# MCU.net
KiCad netlist of a schematic drawn in Altium Designer
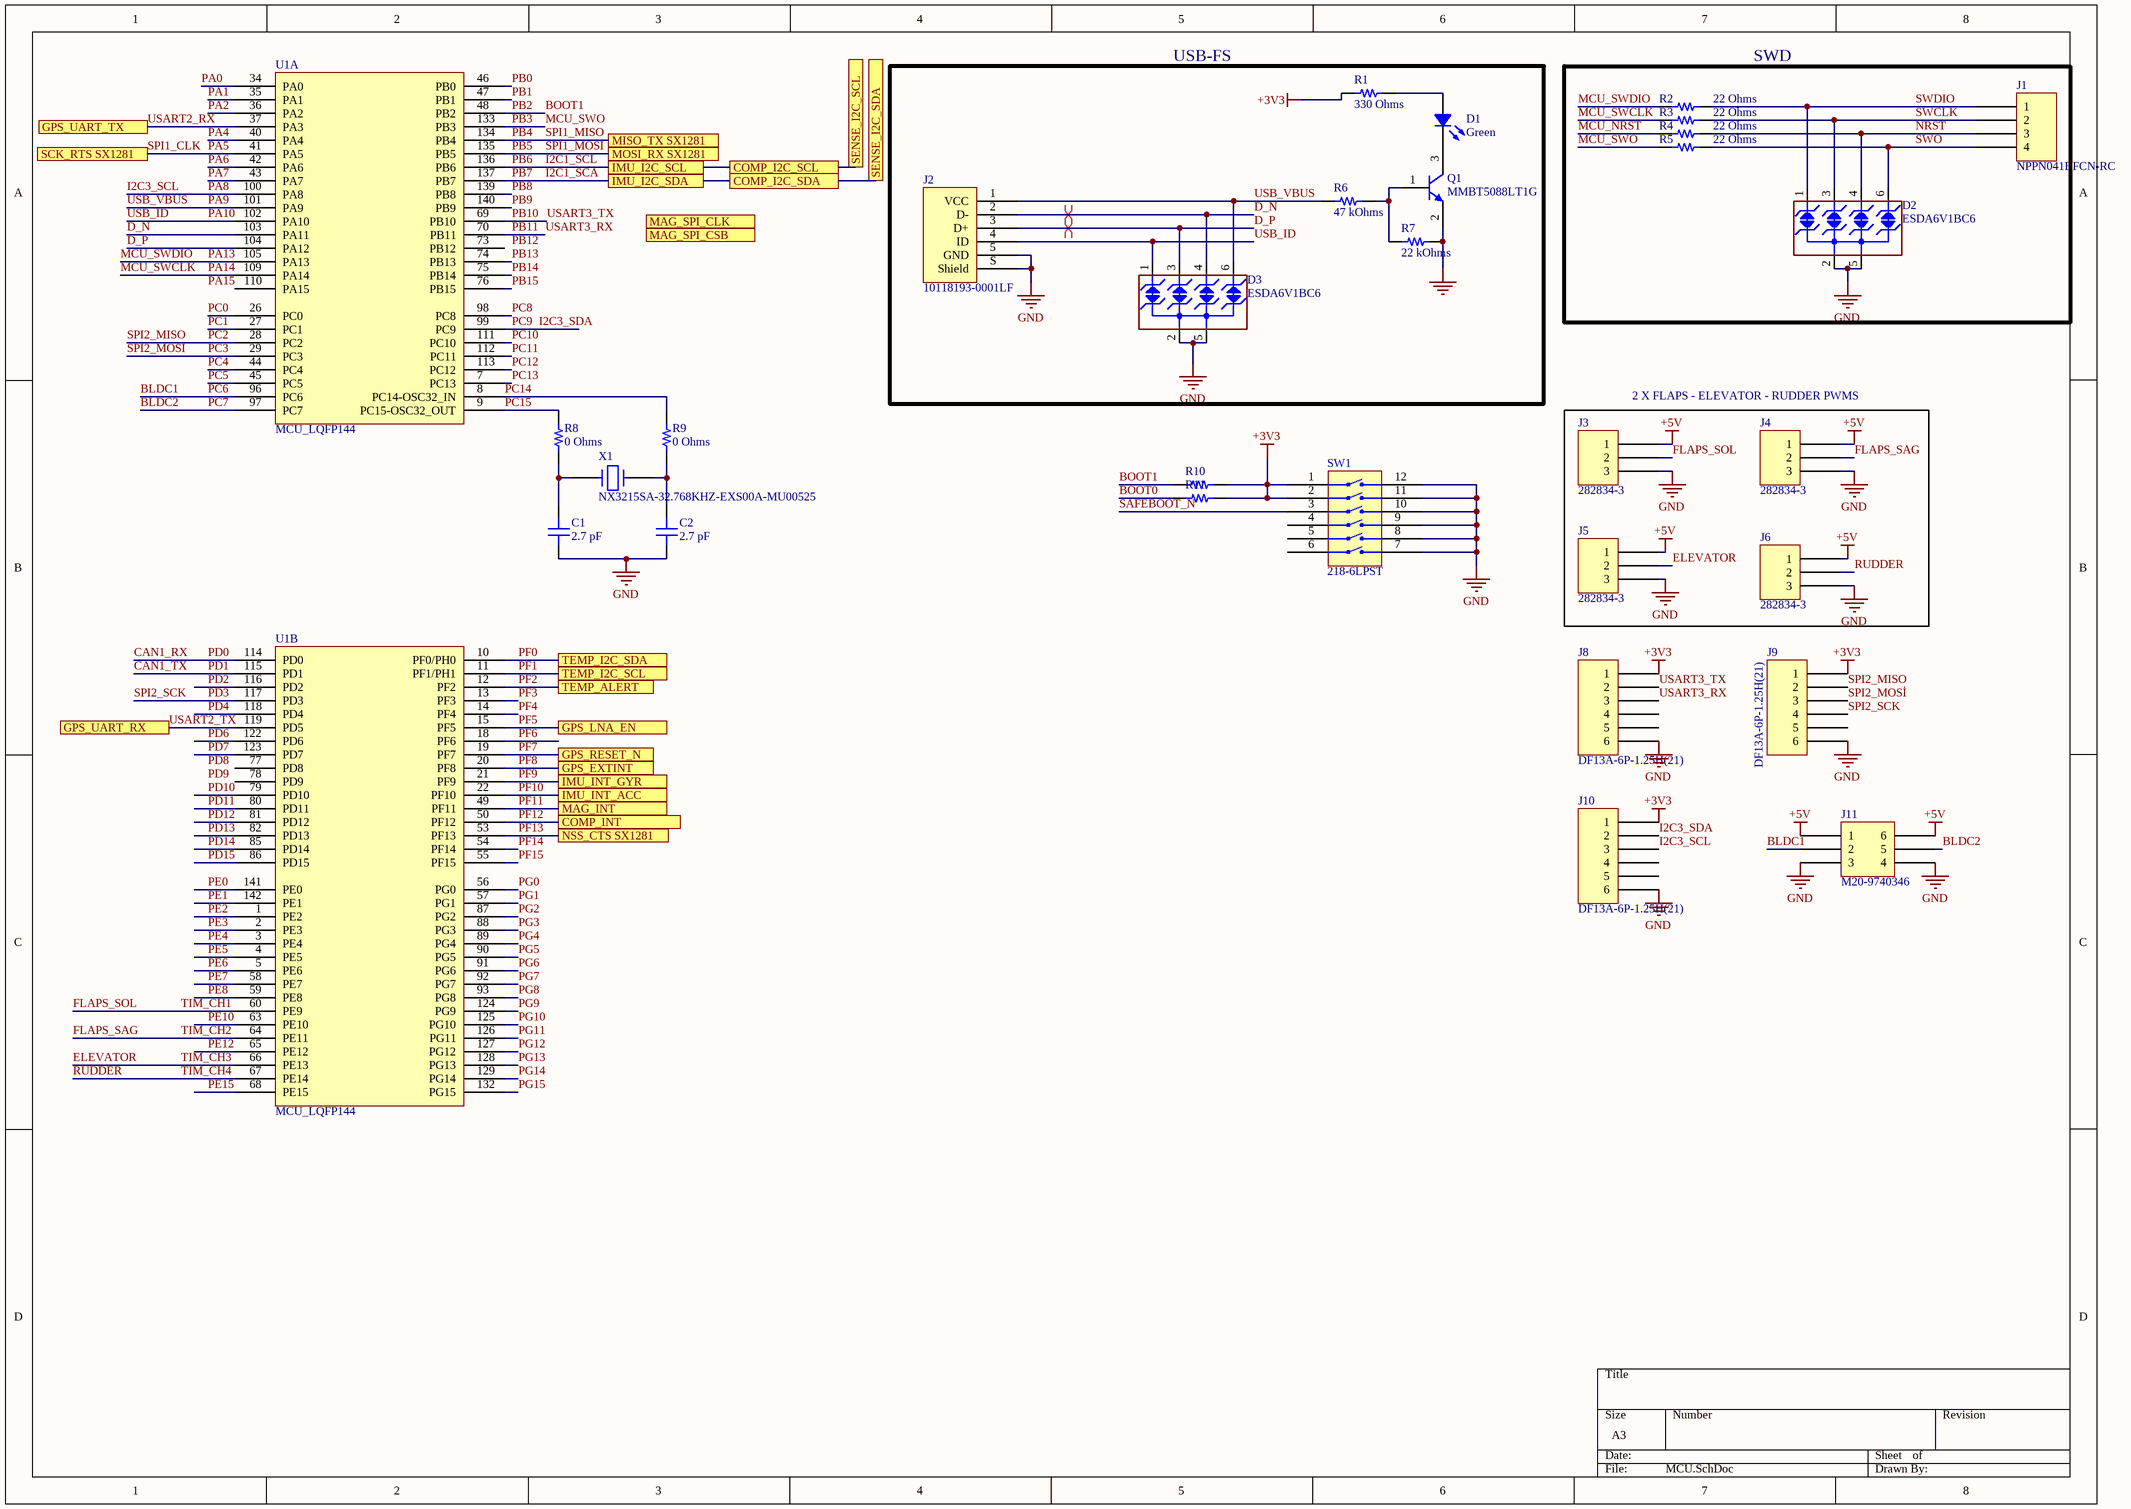
[diagram p0: MCU.SchDoc]

(export (version "E")
  (design (tool "Eeschema 10.0.6"))
  (components
    (comp (ref "C1")
      (value "2.7 pF")
      (footprint "CAP 0603_1608")
      (description "CAP CER 2.7PF 50V C0G/NPO 0603")
      (fields (field (name "PART NUMBER") "CC0603BRNPO9BN2R7") (field (name "MANUFACTURER") "Yageo"))
      (libsource (lib "Celestial Altium Library - altium_library") (part "Capacitor"))
    )
    (comp (ref "C2")
      (value "2.7 pF")
      (footprint "CAP 0603_1608")
      (description "CAP CER 2.7PF 50V C0G/NPO 0603")
      (fields (field (name "PART NUMBER") "CC0603BRNPO9BN2R7") (field (name "MANUFACTURER") "Yageo"))
      (libsource (lib "Celestial Altium Library - altium_library") (part "Capacitor"))
    )
    (comp (ref "D1")
      (value "Green")
      (footprint "LED 0603_1608 GREEN")
      (description "LED GREEN DIFFUSED CHIP SMD")
      (fields (field (name "PART NUMBER") "HSMG-C197") (field (name "MANUFACTURER") "Broadcom Limited"))
      (libsource (lib "Celestial Altium Library - altium_library") (part "LED"))
    )
    (comp (ref "D2")
      (value "ESDA6V1BC6")
      (footprint "SOT23-6L_STM")
      (description "4-line ESD protection")
      (libsource (lib "ECU_2_Project") (part "ESDA6V1BC6"))
    )
    (comp (ref "D3")
      (value "ESDA6V1BC6")
      (footprint "SOT23-6L_STM")
      (description "4-line ESD protection")
      (libsource (lib "Flight_controller v1.0") (part "ESDA6V1BC6"))
    )
    (comp (ref "J1")
      (value "NPPN041BFCN-RC")
      (footprint "SULLINS NPPN041BFCN")
      (description "CONN HDR 4POS 0.079 GOLD PCB")
      (fields (field (name "MANUFACTURER") "Sullins Connector Solutions"))
      (libsource (lib "Celestial Altium Library - altium_library") (part "4 Pin"))
    )
    (comp (ref "J2")
      (value "10118193-0001LF")
      (footprint "FCI USB 10118193-0001LF")
      (description "CONN RCPT USB2.0 MICRO B SMD R/A")
      (fields (field (name "MANUFACTURER") "Amphenol ICC (FCI)"))
      (libsource (lib "Celestial Altium Library - altium_library") (part "USB 2.0 Type B Micro"))
    )
    (comp (ref "J3")
      (value "282834-3")
      (footprint "TE 282834-3")
      (description "TERM BLK 3P SIDE ENT 2.54MM PCB")
      (fields (field (name "MANUFACTURER") "TE Connectivity AMP Connectors") (field (name "VOLTAGE") "150V"))
      (libsource (lib "Celestial Altium Library - altium_library") (part "3 Pin"))
    )
    (comp (ref "J4")
      (value "282834-3")
      (footprint "TE 282834-3")
      (description "TERM BLK 3P SIDE ENT 2.54MM PCB")
      (fields (field (name "MANUFACTURER") "TE Connectivity AMP Connectors") (field (name "VOLTAGE") "150V"))
      (libsource (lib "Celestial Altium Library - altium_library") (part "3 Pin"))
    )
    (comp (ref "J5")
      (value "282834-3")
      (footprint "TE 282834-3")
      (description "TERM BLK 3P SIDE ENT 2.54MM PCB")
      (fields (field (name "MANUFACTURER") "TE Connectivity AMP Connectors") (field (name "VOLTAGE") "150V"))
      (libsource (lib "Celestial Altium Library - altium_library") (part "3 Pin"))
    )
    (comp (ref "J6")
      (value "282834-3")
      (footprint "TE 282834-3")
      (description "TERM BLK 3P SIDE ENT 2.54MM PCB")
      (fields (field (name "MANUFACTURER") "TE Connectivity AMP Connectors") (field (name "VOLTAGE") "150V"))
      (libsource (lib "Celestial Altium Library - altium_library") (part "3 Pin"))
    )
    (comp (ref "J8")
      (value "DF13A-6P-1.25H(21)")
      (footprint "HIROSE DF13A-6P-1.25H")
      (description "CONN HEADER SMD R/A 6POS 1.25MM")
      (fields (field (name "MANUFACTURER") "Hirose Electric Co Ltd"))
      (libsource (lib "Celestial Altium Library - altium_library") (part "6 Pin"))
    )
    (comp (ref "J9")
      (value "DF13A-6P-1.25H(21)")
      (footprint "HIROSE DF13A-6P-1.25H")
      (description "CONN HEADER SMD R/A 6POS 1.25MM")
      (fields (field (name "MANUFACTURER") "Hirose Electric Co Ltd"))
      (libsource (lib "Celestial Altium Library - altium_library") (part "6 Pin"))
    )
    (comp (ref "J10")
      (value "DF13A-6P-1.25H(21)")
      (footprint "HIROSE DF13A-6P-1.25H")
      (description "CONN HEADER SMD R/A 6POS 1.25MM")
      (fields (field (name "MANUFACTURER") "Hirose Electric Co Ltd"))
      (libsource (lib "Celestial Altium Library - altium_library") (part "6 Pin"))
    )
    (comp (ref "J11")
      (value "M20-9740346")
      (footprint "HARWIN M20-9740345")
      (description "CONN HEADER R/A 6POS 2.54MM")
      (fields (field (name "MANUFACTURER") "Harwin Inc."))
      (libsource (lib "Celestial Altium Library - altium_library") (part "2X3 PIN DU"))
    )
    (comp (ref "Q1")
      (value "MMBT5088LT1G")
      (footprint "ON SEMI SOT-23-3")
      (description "TRANS NPN 30V 0.05A SOT23")
      (fields (field (name "MANUFACTURER") "ON Semiconductor"))
      (libsource (lib "Celestial Altium Library - altium_library") (part "ON SEMI NPN SOT-23-3"))
    )
    (comp (ref "R1")
      (value "330 Ohms")
      (footprint "RES 0603_1608")
      (description "RES 330 OHM 1% 1/10W 0603")
      (fields (field (name "PART NUMBER") "RC0603FR-07330RL") (field (name "MANUFACTURER") "Yageo"))
      (libsource (lib "Celestial Altium Library - altium_library") (part "Resistor"))
    )
    (comp (ref "R2")
      (value "22 Ohms")
      (footprint "RES 0603_1608")
      (description "RES 22 OHM 1% 1/10W 0603")
      (fields (field (name "PART NUMBER") "RC0603FR-0722RL") (field (name "MANUFACTURER") "Yageo"))
      (libsource (lib "Celestial Altium Library - altium_library") (part "Resistor"))
    )
    (comp (ref "R3")
      (value "22 Ohms")
      (footprint "RES 0603_1608")
      (description "RES 22 OHM 1% 1/10W 0603")
      (fields (field (name "PART NUMBER") "RC0603FR-0722RL") (field (name "MANUFACTURER") "Yageo"))
      (libsource (lib "Celestial Altium Library - altium_library") (part "Resistor"))
    )
    (comp (ref "R4")
      (value "22 Ohms")
      (footprint "RES 0603_1608")
      (description "RES 22 OHM 1% 1/10W 0603")
      (fields (field (name "PART NUMBER") "RC0603FR-0722RL") (field (name "MANUFACTURER") "Yageo"))
      (libsource (lib "Celestial Altium Library - altium_library") (part "Resistor"))
    )
    (comp (ref "R5")
      (value "22 Ohms")
      (footprint "RES 0603_1608")
      (description "RES 22 OHM 1% 1/10W 0603")
      (fields (field (name "PART NUMBER") "RC0603FR-0722RL") (field (name "MANUFACTURER") "Yageo"))
      (libsource (lib "Celestial Altium Library - altium_library") (part "Resistor"))
    )
    (comp (ref "R6")
      (value "47 kOhms")
      (footprint "RES 0603_1608")
      (description "RES 47K OHM 1% 1/10W 0603")
      (fields (field (name "PART NUMBER") "RC0603FR-0747KL") (field (name "MANUFACTURER") "Yageo"))
      (libsource (lib "Celestial Altium Library - altium_library") (part "Resistor"))
    )
    (comp (ref "R7")
      (value "22 kOhms")
      (footprint "RES 0603_1608")
      (description "RES 22K OHM 1% 1/10W 0603")
      (fields (field (name "PART NUMBER") "RC0603FR-0722KL") (field (name "MANUFACTURER") "Yageo"))
      (libsource (lib "Celestial Altium Library - altium_library") (part "Resistor"))
    )
    (comp (ref "R8")
      (value "0 Ohms")
      (footprint "RES 0603_1608")
      (description "RES 0 OHM JUMPER 1/10W 0603")
      (fields (field (name "PART NUMBER") "RC0603JR-070RL") (field (name "MANUFACTURER") "Yageo"))
      (libsource (lib "Celestial Altium Library - altium_library") (part "Resistor"))
    )
    (comp (ref "R9")
      (value "0 Ohms")
      (footprint "RES 0603_1608")
      (description "RES 0 OHM JUMPER 1/10W 0603")
      (fields (field (name "PART NUMBER") "RC0603JR-070RL") (field (name "MANUFACTURER") "Yageo"))
      (libsource (lib "Celestial Altium Library - altium_library") (part "Resistor"))
    )
    (comp (ref "R10")
      (value "100 kOhms")
      (footprint "RES 0603_1608")
      (description "RES 100K OHM 1% 1/10W 0603")
      (fields (field (name "PART NUMBER") "RC0603FR-07100KL") (field (name "MANUFACTURER") "Yageo"))
      (libsource (lib "Celestial Altium Library - altium_library") (part "Resistor"))
    )
    (comp (ref "R11")
      (value "10 kOhms")
      (footprint "RES 0603_1608")
      (description "RES 10K OHM 1% 1/10W 0603")
      (fields (field (name "PART NUMBER") "RC0603FR-0710KL") (field (name "MANUFACTURER") "Yageo"))
      (libsource (lib "Celestial Altium Library - altium_library") (part "Resistor"))
    )
    (comp (ref "SW1")
      (value "218-6LPST")
      (footprint "CTS 218-6LPJ")
      (description "SWITCH SLIDE DIP SPST 25MA 24V")
      (fields (field (name "MANUFACTURER") "CTS Electrocomponents"))
      (libsource (lib "Celestial Altium Library - altium_library") (part "DIP SW 6P"))
    )
    (comp (ref "U1")
      (value "MCU_LQFP144")
      (footprint "LQFP144-20x20mm")
      (libsource (lib "MB1137") (part "MCU_LQFP144"))
    )
    (comp (ref "X1")
      (value "NX3215SA-32.768KHZ-EXS00A-MU00525")
      (footprint "XTAL_NX3215SA-32.768KHZ-EXS00A-MU00525_NDK")
      (description "Crystal")
      (libsource (lib "Flight_controller v1.0") (part "CRYSTAL_32K"))
    )
  )
  (nets
    (net (code "1") (name "+3V3") (class "Default")
      (node (ref "J10") (pin "1") (pinfunction "1_1") (pintype "passive"))
      (node (ref "J8") (pin "1") (pinfunction "1_1") (pintype "passive"))
      (node (ref "J9") (pin "1") (pinfunction "1_1") (pintype "passive"))
      (node (ref "R1") (pin "2") (pinfunction "2_2") (pintype "passive"))
      (node (ref "R10") (pin "2") (pinfunction "2_2") (pintype "passive"))
      (node (ref "R11") (pin "2") (pinfunction "2_2") (pintype "passive"))
      (node (ref "SW1") (pin "1") (pinfunction "GND_1") (pintype "passive"))
      (node (ref "SW1") (pin "2") (pinfunction "GND_2") (pintype "passive"))
    )
    (net (code "2") (name "+5V") (class "Default")
      (node (ref "J11") (pin "1") (pinfunction "1_1") (pintype "passive"))
      (node (ref "J11") (pin "6") (pinfunction "6_6") (pintype "passive"))
      (node (ref "J3") (pin "1") (pinfunction "1_1") (pintype "passive"))
      (node (ref "J4") (pin "1") (pinfunction "1_1") (pintype "passive"))
      (node (ref "J5") (pin "1") (pinfunction "1_1") (pintype "passive"))
      (node (ref "J6") (pin "1") (pinfunction "1_1") (pintype "passive"))
    )
    (net (code "3") (name "/BLDC1") (class "Default")
      (node (ref "J11") (pin "2") (pinfunction "2_2") (pintype "passive"))
      (node (ref "U1") (pin "96") (pinfunction "PC6_96") (pintype "passive"))
    )
    (net (code "4") (name "/BLDC2") (class "Default")
      (node (ref "J11") (pin "5") (pinfunction "5_5") (pintype "passive"))
      (node (ref "U1") (pin "97") (pinfunction "PC7_97") (pintype "passive"))
    )
    (net (code "5") (name "/BOOT0") (class "Default")
      (node (ref "R11") (pin "1") (pinfunction "1_1") (pintype "passive"))
    )
    (net (code "6") (name "/BOOT1") (class "Default")
      (node (ref "R10") (pin "1") (pinfunction "1_1") (pintype "passive"))
      (node (ref "U1") (pin "48") (pinfunction "PB2_48") (pintype "passive"))
    )
    (net (code "7") (name "/CAN1_RX") (class "Default")
      (node (ref "U1") (pin "114") (pinfunction "PD0_114") (pintype "passive"))
    )
    (net (code "8") (name "/CAN1_TX") (class "Default")
      (node (ref "U1") (pin "115") (pinfunction "PD1_115") (pintype "passive"))
    )
    (net (code "9") (name "/D_N") (class "Default")
      (node (ref "D3") (pin "4") (pinfunction "IO3_4") (pintype "passive"))
      (node (ref "J2") (pin "2") (pinfunction "D-_2") (pintype "passive"))
      (node (ref "U1") (pin "103") (pinfunction "PA11_103") (pintype "passive"))
    )
    (net (code "10") (name "/D_P") (class "Default")
      (node (ref "D3") (pin "3") (pinfunction "GND_3") (pintype "passive"))
      (node (ref "J2") (pin "3") (pinfunction "D+_3") (pintype "passive"))
      (node (ref "U1") (pin "104") (pinfunction "PA12_104") (pintype "passive"))
    )
    (net (code "11") (name "/ELEVATOR") (class "Default")
      (node (ref "J5") (pin "2") (pinfunction "2_2") (pintype "passive"))
      (node (ref "U1") (pin "66") (pinfunction "PE13_66") (pintype "passive"))
    )
    (net (code "12") (name "/FLAPS_SAG") (class "Default")
      (node (ref "J4") (pin "2") (pinfunction "2_2") (pintype "passive"))
      (node (ref "U1") (pin "64") (pinfunction "PE11_64") (pintype "passive"))
    )
    (net (code "13") (name "/FLAPS_SOL") (class "Default")
      (node (ref "J3") (pin "2") (pinfunction "2_2") (pintype "passive"))
      (node (ref "U1") (pin "60") (pinfunction "PE9_60") (pintype "passive"))
    )
    (net (code "14") (name "/I2C1_SCA") (class "Default")
      (node (ref "U1") (pin "137") (pinfunction "PB7_137") (pintype "passive"))
    )
    (net (code "15") (name "/I2C1_SCL") (class "Default")
      (node (ref "U1") (pin "136") (pinfunction "PB6_136") (pintype "passive"))
    )
    (net (code "16") (name "/I2C3_SCL") (class "Default")
      (node (ref "J10") (pin "3") (pinfunction "3_3") (pintype "passive"))
      (node (ref "U1") (pin "100") (pinfunction "PA8_100") (pintype "passive"))
    )
    (net (code "17") (name "/I2C3_SDA") (class "Default")
      (node (ref "J10") (pin "2") (pinfunction "2_2") (pintype "passive"))
      (node (ref "U1") (pin "99") (pinfunction "PC9_99") (pintype "passive"))
    )
    (net (code "20") (name "/MCU_NRST") (class "Default")
      (node (ref "R4") (pin "1") (pinfunction "1_1") (pintype "passive"))
    )
    (net (code "21") (name "/MCU_SWCLK") (class "Default")
      (node (ref "R3") (pin "1") (pinfunction "1_1") (pintype "passive"))
      (node (ref "U1") (pin "109") (pinfunction "PA14_109") (pintype "passive"))
    )
    (net (code "22") (name "/MCU_SWDIO") (class "Default")
      (node (ref "R2") (pin "1") (pinfunction "1_1") (pintype "passive"))
      (node (ref "U1") (pin "105") (pinfunction "PA13_105") (pintype "passive"))
    )
    (net (code "23") (name "/MCU_SWO") (class "Default")
      (node (ref "R5") (pin "1") (pinfunction "1_1") (pintype "passive"))
      (node (ref "U1") (pin "133") (pinfunction "PB3_133") (pintype "passive"))
    )
    (net (code "24") (name "/NRST") (class "Default")
      (node (ref "D2") (pin "4") (pinfunction "IO3_4") (pintype "passive"))
      (node (ref "J1") (pin "3") (pinfunction "3_3") (pintype "passive"))
      (node (ref "R4") (pin "2") (pinfunction "2_2") (pintype "passive"))
    )
    (net (code "25") (name "/PA0") (class "Default")
      (node (ref "U1") (pin "34") (pinfunction "PA0_34") (pintype "passive"))
    )
    (net (code "26") (name "/PA1") (class "Default")
      (node (ref "U1") (pin "35") (pinfunction "PA1_35") (pintype "passive"))
    )
    (net (code "27") (name "/PA2") (class "Default")
      (node (ref "U1") (pin "36") (pinfunction "PA2_36") (pintype "passive"))
    )
    (net (code "28") (name "/PA4") (class "Default")
      (node (ref "U1") (pin "40") (pinfunction "PA4_40") (pintype "passive"))
    )
    (net (code "29") (name "/PA5") (class "Default")
      (node (ref "U1") (pin "41") (pinfunction "PA5_41") (pintype "passive"))
    )
    (net (code "30") (name "/PA6") (class "Default")
      (node (ref "U1") (pin "42") (pinfunction "PA6_42") (pintype "passive"))
    )
    (net (code "31") (name "/PA7") (class "Default")
      (node (ref "U1") (pin "43") (pinfunction "PA7_43") (pintype "passive"))
    )
    (net (code "32") (name "/PA9") (class "Default")
      (node (ref "D3") (pin "6") (pinfunction "NC_6") (pintype "passive"))
      (node (ref "J2") (pin "1") (pinfunction "VCC_1") (pintype "passive"))
      (node (ref "R6") (pin "1") (pinfunction "1_1") (pintype "passive"))
      (node (ref "U1") (pin "101") (pinfunction "PA9_101") (pintype "passive"))
    )
    (net (code "33") (name "/PA10") (class "Default")
      (node (ref "D3") (pin "1") (pinfunction "IO1_1") (pintype "passive"))
      (node (ref "J2") (pin "4") (pinfunction "ID_4") (pintype "passive"))
      (node (ref "U1") (pin "102") (pinfunction "PA10_102") (pintype "passive"))
    )
    (net (code "35") (name "/PB0") (class "Default")
      (node (ref "U1") (pin "46") (pinfunction "PB0_46") (pintype "passive"))
    )
    (net (code "36") (name "/PB1") (class "Default")
      (node (ref "U1") (pin "47") (pinfunction "PB1_47") (pintype "passive"))
    )
    (net (code "37") (name "/PB4") (class "Default")
      (node (ref "U1") (pin "134") (pinfunction "PB4_134") (pintype "passive"))
    )
    (net (code "38") (name "/PB5") (class "Default")
      (node (ref "U1") (pin "135") (pinfunction "PB5_135") (pintype "passive"))
    )
    (net (code "39") (name "/PB8") (class "Default")
      (node (ref "U1") (pin "139") (pinfunction "PB8_139") (pintype "passive"))
    )
    (net (code "40") (name "/PB9") (class "Default")
      (node (ref "U1") (pin "140") (pinfunction "PB9_140") (pintype "passive"))
    )
    (net (code "41") (name "/PB10") (class "Default")
      (node (ref "J8") (pin "2") (pinfunction "2_2") (pintype "passive"))
      (node (ref "U1") (pin "69") (pinfunction "PB10_69") (pintype "passive"))
    )
    (net (code "42") (name "/PB11") (class "Default")
      (node (ref "J8") (pin "3") (pinfunction "3_3") (pintype "passive"))
      (node (ref "U1") (pin "70") (pinfunction "PB11_70") (pintype "passive"))
    )
    (net (code "44") (name "/PB13") (class "Default")
      (node (ref "U1") (pin "74") (pinfunction "PB13_74") (pintype "passive"))
    )
    (net (code "45") (name "/PB14") (class "Default")
      (node (ref "U1") (pin "75") (pinfunction "PB14_75") (pintype "passive"))
    )
    (net (code "46") (name "/PB15") (class "Default")
      (node (ref "U1") (pin "76") (pinfunction "PB15_76") (pintype "passive"))
    )
    (net (code "47") (name "/PC0") (class "Default")
      (node (ref "U1") (pin "26") (pinfunction "PC0_26") (pintype "passive"))
    )
    (net (code "48") (name "/PC1") (class "Default")
      (node (ref "U1") (pin "27") (pinfunction "PC1_27") (pintype "passive"))
    )
    (net (code "49") (name "/PC2") (class "Default")
      (node (ref "J9") (pin "2") (pinfunction "2_2") (pintype "passive"))
      (node (ref "U1") (pin "28") (pinfunction "PC2_28") (pintype "passive"))
    )
    (net (code "50") (name "/PC3") (class "Default")
      (node (ref "J9") (pin "3") (pinfunction "3_3") (pintype "passive"))
      (node (ref "U1") (pin "29") (pinfunction "PC3_29") (pintype "passive"))
    )
    (net (code "51") (name "/PC4") (class "Default")
      (node (ref "U1") (pin "44") (pinfunction "PC4_44") (pintype "passive"))
    )
    (net (code "52") (name "/PC5") (class "Default")
      (node (ref "U1") (pin "45") (pinfunction "PC5_45") (pintype "passive"))
    )
    (net (code "53") (name "/PC8") (class "Default")
      (node (ref "U1") (pin "98") (pinfunction "PC8_98") (pintype "passive"))
    )
    (net (code "54") (name "/PC10") (class "Default")
      (node (ref "U1") (pin "111") (pinfunction "PC10_111") (pintype "passive"))
    )
    (net (code "55") (name "/PC11") (class "Default")
      (node (ref "U1") (pin "112") (pinfunction "PC11_112") (pintype "passive"))
    )
    (net (code "56") (name "/PC12") (class "Default")
      (node (ref "U1") (pin "113") (pinfunction "PC12_113") (pintype "passive"))
    )
    (net (code "57") (name "/PC13") (class "Default")
      (node (ref "U1") (pin "7") (pinfunction "PC13_7") (pintype "passive"))
    )
    (net (code "58") (name "/PC14") (class "Default")
      (node (ref "R9") (pin "2") (pinfunction "2_2") (pintype "passive"))
      (node (ref "U1") (pin "8") (pinfunction "PC14-OSC32_IN_8") (pintype "passive"))
    )
    (net (code "59") (name "/PC15") (class "Default")
      (node (ref "R8") (pin "2") (pinfunction "2_2") (pintype "passive"))
      (node (ref "U1") (pin "9") (pinfunction "PC15-OSC32_OUT_9") (pintype "passive"))
    )
    (net (code "60") (name "/PD2") (class "Default")
      (node (ref "U1") (pin "116") (pinfunction "PD2_116") (pintype "passive"))
    )
    (net (code "61") (name "/PD3") (class "Default")
      (node (ref "J9") (pin "4") (pinfunction "4_4") (pintype "passive"))
      (node (ref "U1") (pin "117") (pinfunction "PD3_117") (pintype "passive"))
    )
    (net (code "62") (name "/PD4") (class "Default")
      (node (ref "U1") (pin "118") (pinfunction "PD4_118") (pintype "passive"))
    )
    (net (code "63") (name "/PD6") (class "Default")
      (node (ref "U1") (pin "122") (pinfunction "PD6_122") (pintype "passive"))
    )
    (net (code "64") (name "/PD7") (class "Default")
      (node (ref "U1") (pin "123") (pinfunction "PD7_123") (pintype "passive"))
    )
    (net (code "67") (name "/PD10") (class "Default")
      (node (ref "U1") (pin "79") (pinfunction "PD10_79") (pintype "passive"))
    )
    (net (code "68") (name "/PD11") (class "Default")
      (node (ref "U1") (pin "80") (pinfunction "PD11_80") (pintype "passive"))
    )
    (net (code "69") (name "/PD12") (class "Default")
      (node (ref "U1") (pin "81") (pinfunction "PD12_81") (pintype "passive"))
    )
    (net (code "70") (name "/PD13") (class "Default")
      (node (ref "U1") (pin "82") (pinfunction "PD13_82") (pintype "passive"))
    )
    (net (code "71") (name "/PD14") (class "Default")
      (node (ref "U1") (pin "85") (pinfunction "PD14_85") (pintype "passive"))
    )
    (net (code "72") (name "/PD15") (class "Default")
      (node (ref "U1") (pin "86") (pinfunction "PD15_86") (pintype "passive"))
    )
    (net (code "73") (name "/PE0") (class "Default")
      (node (ref "U1") (pin "141") (pinfunction "PE0_141") (pintype "passive"))
    )
    (net (code "74") (name "/PE1") (class "Default")
      (node (ref "U1") (pin "142") (pinfunction "PE1_142") (pintype "passive"))
    )
    (net (code "75") (name "/PE2") (class "Default")
      (node (ref "U1") (pin "1") (pinfunction "PE2_1") (pintype "passive"))
    )
    (net (code "76") (name "/PE3") (class "Default")
      (node (ref "U1") (pin "2") (pinfunction "PE3_2") (pintype "passive"))
    )
    (net (code "77") (name "/PE4") (class "Default")
      (node (ref "U1") (pin "3") (pinfunction "PE4_3") (pintype "passive"))
    )
    (net (code "78") (name "/PE5") (class "Default")
      (node (ref "U1") (pin "4") (pinfunction "PE5_4") (pintype "passive"))
    )
    (net (code "79") (name "/PE6") (class "Default")
      (node (ref "U1") (pin "5") (pinfunction "PE6_5") (pintype "passive"))
    )
    (net (code "80") (name "/PE7") (class "Default")
      (node (ref "U1") (pin "58") (pinfunction "PE7_58") (pintype "passive"))
    )
    (net (code "81") (name "/PE8") (class "Default")
      (node (ref "U1") (pin "59") (pinfunction "PE8_59") (pintype "passive"))
    )
    (net (code "82") (name "/PE10") (class "Default")
      (node (ref "U1") (pin "63") (pinfunction "PE10_63") (pintype "passive"))
    )
    (net (code "83") (name "/PE12") (class "Default")
      (node (ref "U1") (pin "65") (pinfunction "PE12_65") (pintype "passive"))
    )
    (net (code "84") (name "/PE15") (class "Default")
      (node (ref "U1") (pin "68") (pinfunction "PE15_68") (pintype "passive"))
    )
    (net (code "85") (name "/PF0") (class "Default")
      (node (ref "U1") (pin "10") (pinfunction "PF0/PH0_10") (pintype "passive"))
    )
    (net (code "86") (name "/PF1") (class "Default")
      (node (ref "U1") (pin "11") (pinfunction "PF1/PH1_11") (pintype "passive"))
    )
    (net (code "87") (name "/PF2") (class "Default")
      (node (ref "U1") (pin "12") (pinfunction "PF2_12") (pintype "passive"))
    )
    (net (code "88") (name "/PF3") (class "Default")
      (node (ref "U1") (pin "13") (pinfunction "PF3_13") (pintype "passive"))
    )
    (net (code "89") (name "/PF4") (class "Default")
      (node (ref "U1") (pin "14") (pinfunction "PF4_14") (pintype "passive"))
    )
    (net (code "90") (name "/PF5") (class "Default")
      (node (ref "U1") (pin "15") (pinfunction "PF5_15") (pintype "passive"))
    )
    (net (code "91") (name "/PF6") (class "Default")
      (node (ref "U1") (pin "18") (pinfunction "PF6_18") (pintype "passive"))
    )
    (net (code "92") (name "/PF7") (class "Default")
      (node (ref "U1") (pin "19") (pinfunction "PF7_19") (pintype "passive"))
    )
    (net (code "93") (name "/PF8") (class "Default")
      (node (ref "U1") (pin "20") (pinfunction "PF8_20") (pintype "passive"))
    )
    (net (code "94") (name "/PF9") (class "Default")
      (node (ref "U1") (pin "21") (pinfunction "PF9_21") (pintype "passive"))
    )
    (net (code "95") (name "/PF10") (class "Default")
      (node (ref "U1") (pin "22") (pinfunction "PF10_22") (pintype "passive"))
    )
    (net (code "96") (name "/PF11") (class "Default")
      (node (ref "U1") (pin "49") (pinfunction "PF11_49") (pintype "passive"))
    )
    (net (code "97") (name "/PF12") (class "Default")
      (node (ref "U1") (pin "50") (pinfunction "PF12_50") (pintype "passive"))
    )
    (net (code "98") (name "/PF13") (class "Default")
      (node (ref "U1") (pin "53") (pinfunction "PF13_53") (pintype "passive"))
    )
    (net (code "99") (name "/PF14") (class "Default")
      (node (ref "U1") (pin "54") (pinfunction "PF14_54") (pintype "passive"))
    )
    (net (code "100") (name "/PF15") (class "Default")
      (node (ref "U1") (pin "55") (pinfunction "PF15_55") (pintype "passive"))
    )
    (net (code "101") (name "/PG0") (class "Default")
      (node (ref "U1") (pin "56") (pinfunction "PG0_56") (pintype "passive"))
    )
    (net (code "102") (name "/PG1") (class "Default")
      (node (ref "U1") (pin "57") (pinfunction "PG1_57") (pintype "passive"))
    )
    (net (code "103") (name "/PG2") (class "Default")
      (node (ref "U1") (pin "87") (pinfunction "PG2_87") (pintype "passive"))
    )
    (net (code "104") (name "/PG3") (class "Default")
      (node (ref "U1") (pin "88") (pinfunction "PG3_88") (pintype "passive"))
    )
    (net (code "105") (name "/PG4") (class "Default")
      (node (ref "U1") (pin "89") (pinfunction "PG4_89") (pintype "passive"))
    )
    (net (code "106") (name "/PG5") (class "Default")
      (node (ref "U1") (pin "90") (pinfunction "PG5_90") (pintype "passive"))
    )
    (net (code "107") (name "/PG6") (class "Default")
      (node (ref "U1") (pin "91") (pinfunction "PG6_91") (pintype "passive"))
    )
    (net (code "108") (name "/PG7") (class "Default")
      (node (ref "U1") (pin "92") (pinfunction "PG7_92") (pintype "passive"))
    )
    (net (code "109") (name "/PG8") (class "Default")
      (node (ref "U1") (pin "93") (pinfunction "PG8_93") (pintype "passive"))
    )
    (net (code "110") (name "/PG9") (class "Default")
      (node (ref "U1") (pin "124") (pinfunction "PG9_124") (pintype "passive"))
    )
    (net (code "111") (name "/PG10") (class "Default")
      (node (ref "U1") (pin "125") (pinfunction "PG10_125") (pintype "passive"))
    )
    (net (code "112") (name "/PG11") (class "Default")
      (node (ref "U1") (pin "126") (pinfunction "PG11_126") (pintype "passive"))
    )
    (net (code "113") (name "/PG12") (class "Default")
      (node (ref "U1") (pin "127") (pinfunction "PG12_127") (pintype "passive"))
    )
    (net (code "114") (name "/PG13") (class "Default")
      (node (ref "U1") (pin "128") (pinfunction "PG13_128") (pintype "passive"))
    )
    (net (code "115") (name "/PG14") (class "Default")
      (node (ref "U1") (pin "129") (pinfunction "PG14_129") (pintype "passive"))
    )
    (net (code "116") (name "/PG15") (class "Default")
      (node (ref "U1") (pin "132") (pinfunction "PG15_132") (pintype "passive"))
    )
    (net (code "117") (name "/RUDDER") (class "Default")
      (node (ref "J6") (pin "2") (pinfunction "2_2") (pintype "passive"))
      (node (ref "U1") (pin "67") (pinfunction "PE14_67") (pintype "passive"))
    )
    (net (code "118") (name "/SAFEBOOT_N") (class "Default")
      (node (ref "SW1") (pin "3") (pinfunction "GND_3") (pintype "passive"))
    )
    (net (code "119") (name "/SWCLK") (class "Default")
      (node (ref "D2") (pin "3") (pinfunction "GND_3") (pintype "passive"))
      (node (ref "J1") (pin "2") (pinfunction "2_2") (pintype "passive"))
      (node (ref "R3") (pin "2") (pinfunction "2_2") (pintype "passive"))
    )
    (net (code "120") (name "/SWDIO") (class "Default")
      (node (ref "D2") (pin "1") (pinfunction "IO1_1") (pintype "passive"))
      (node (ref "J1") (pin "1") (pinfunction "1_1") (pintype "passive"))
      (node (ref "R2") (pin "2") (pinfunction "2_2") (pintype "passive"))
    )
    (net (code "121") (name "/SWO") (class "Default")
      (node (ref "D2") (pin "6") (pinfunction "NC_6") (pintype "passive"))
      (node (ref "J1") (pin "4") (pinfunction "4_4") (pintype "passive"))
      (node (ref "R5") (pin "2") (pinfunction "2_2") (pintype "passive"))
    )
    (net (code "122") (name "/USART2_RX") (class "Default")
      (node (ref "U1") (pin "37") (pinfunction "PA3_37") (pintype "passive"))
    )
    (net (code "123") (name "/USART2_TX") (class "Default")
      (node (ref "U1") (pin "119") (pinfunction "PD5_119") (pintype "passive"))
    )
    (net (code "124") (name "GND") (class "Default")
      (node (ref "C1") (pin "1") (pinfunction "1_1") (pintype "passive"))
      (node (ref "C2") (pin "1") (pinfunction "1_1") (pintype "passive"))
      (node (ref "D2") (pin "2") (pinfunction "IO2_2") (pintype "passive"))
      (node (ref "D2") (pin "5") (pinfunction "IO4_5") (pintype "passive"))
      (node (ref "D3") (pin "2") (pinfunction "IO2_2") (pintype "passive"))
      (node (ref "D3") (pin "5") (pinfunction "IO4_5") (pintype "passive"))
      (node (ref "J10") (pin "6") (pinfunction "6_6") (pintype "passive"))
      (node (ref "J11") (pin "3") (pinfunction "3_3") (pintype "passive"))
      (node (ref "J11") (pin "4") (pinfunction "4_4") (pintype "passive"))
      (node (ref "J2") (pin "5") (pinfunction "GND_5") (pintype "passive"))
      (node (ref "J2") (pin "S") (pinfunction "Shield_S") (pintype "passive"))
      (node (ref "J3") (pin "3") (pinfunction "3_3") (pintype "passive"))
      (node (ref "J4") (pin "3") (pinfunction "3_3") (pintype "passive"))
      (node (ref "J5") (pin "3") (pinfunction "3_3") (pintype "passive"))
      (node (ref "J6") (pin "3") (pinfunction "3_3") (pintype "passive"))
      (node (ref "J8") (pin "6") (pinfunction "6_6") (pintype "passive"))
      (node (ref "J9") (pin "6") (pinfunction "6_6") (pintype "passive"))
      (node (ref "Q1") (pin "2") (pinfunction "E_2") (pintype "passive"))
      (node (ref "R7") (pin "2") (pinfunction "2_2") (pintype "passive"))
      (node (ref "SW1") (pin "10") (pinfunction "10_10") (pintype "passive"))
      (node (ref "SW1") (pin "11") (pinfunction "11_11") (pintype "passive"))
      (node (ref "SW1") (pin "12") (pinfunction "12_12") (pintype "passive"))
      (node (ref "SW1") (pin "7") (pinfunction "7_7") (pintype "passive"))
      (node (ref "SW1") (pin "8") (pinfunction "8_8") (pintype "passive"))
      (node (ref "SW1") (pin "9") (pinfunction "9_9") (pintype "passive"))
    )
    (net (code "125") (name "Net-(C1-Pad2)") (class "Default")
      (node (ref "C1") (pin "2") (pinfunction "2_2") (pintype "passive"))
      (node (ref "R8") (pin "1") (pinfunction "1_1") (pintype "passive"))
      (node (ref "X1") (pin "1") (pinfunction "1_1") (pintype "passive"))
    )
    (net (code "126") (name "Net-(C2-Pad2)") (class "Default")
      (node (ref "C2") (pin "2") (pinfunction "2_2") (pintype "passive"))
      (node (ref "R9") (pin "1") (pinfunction "1_1") (pintype "passive"))
      (node (ref "X1") (pin "2") (pinfunction "2_2") (pintype "passive"))
    )
    (net (code "127") (name "Net-(D1-Pad1)") (class "Default")
      (node (ref "D1") (pin "1") (pinfunction "1_1") (pintype "passive"))
      (node (ref "R1") (pin "1") (pinfunction "1_1") (pintype "passive"))
    )
    (net (code "128") (name "Net-(Q1-B)") (class "Default")
      (node (ref "Q1") (pin "1") (pinfunction "B_1") (pintype "passive"))
      (node (ref "R6") (pin "2") (pinfunction "2_2") (pintype "passive"))
      (node (ref "R7") (pin "1") (pinfunction "1_1") (pintype "passive"))
    )
    (net (code "129") (name "Net-(Q1-C)") (class "Default")
      (node (ref "D1") (pin "2") (pinfunction "2_2") (pintype "passive"))
      (node (ref "Q1") (pin "3") (pinfunction "C_3") (pintype "passive"))
    )
    (net (code "130") (name "unconnected-(J8-Pad4)") (class "Default")
      (node (ref "J8") (pin "4") (pinfunction "4_4") (pintype "passive"))
    )
    (net (code "131") (name "unconnected-(J8-Pad5)") (class "Default")
      (node (ref "J8") (pin "5") (pinfunction "5_5") (pintype "passive"))
    )
    (net (code "132") (name "unconnected-(J9-Pad5)") (class "Default")
      (node (ref "J9") (pin "5") (pinfunction "5_5") (pintype "passive"))
    )
    (net (code "133") (name "unconnected-(J10-Pad4)") (class "Default")
      (node (ref "J10") (pin "4") (pinfunction "4_4") (pintype "passive"))
    )
    (net (code "134") (name "unconnected-(J10-Pad5)") (class "Default")
      (node (ref "J10") (pin "5") (pinfunction "5_5") (pintype "passive"))
    )
    (net (code "135") (name "unconnected-(SW1-GND-Pad4)") (class "Default")
      (node (ref "SW1") (pin "4") (pinfunction "GND_4") (pintype "passive"))
    )
    (net (code "136") (name "unconnected-(SW1-Pad5)") (class "Default")
      (node (ref "SW1") (pin "5") (pinfunction "5_5") (pintype "passive"))
    )
    (net (code "137") (name "unconnected-(SW1-Pad6)") (class "Default")
      (node (ref "SW1") (pin "6") (pinfunction "6_6") (pintype "passive"))
    )
    (net (code "138") (name "unconnected-(U1A-PA15-Pad110)") (class "Default")
      (node (ref "U1") (pin "110") (pinfunction "PA15_110") (pintype "passive"))
    )
    (net (code "139") (name "unconnected-(U1A-PB12-Pad73)") (class "Default")
      (node (ref "U1") (pin "73") (pinfunction "PB12_73") (pintype "passive"))
    )
    (net (code "140") (name "unconnected-(U1B-PD8-Pad77)") (class "Default")
      (node (ref "U1") (pin "77") (pinfunction "PD8_77") (pintype "passive"))
    )
    (net (code "141") (name "unconnected-(U1B-PD9-Pad78)") (class "Default")
      (node (ref "U1") (pin "78") (pinfunction "PD9_78") (pintype "passive"))
    )
  )
)
